# attiny85usb_4ch.net
KiCad netlist of a schematic drawn in EAGLE
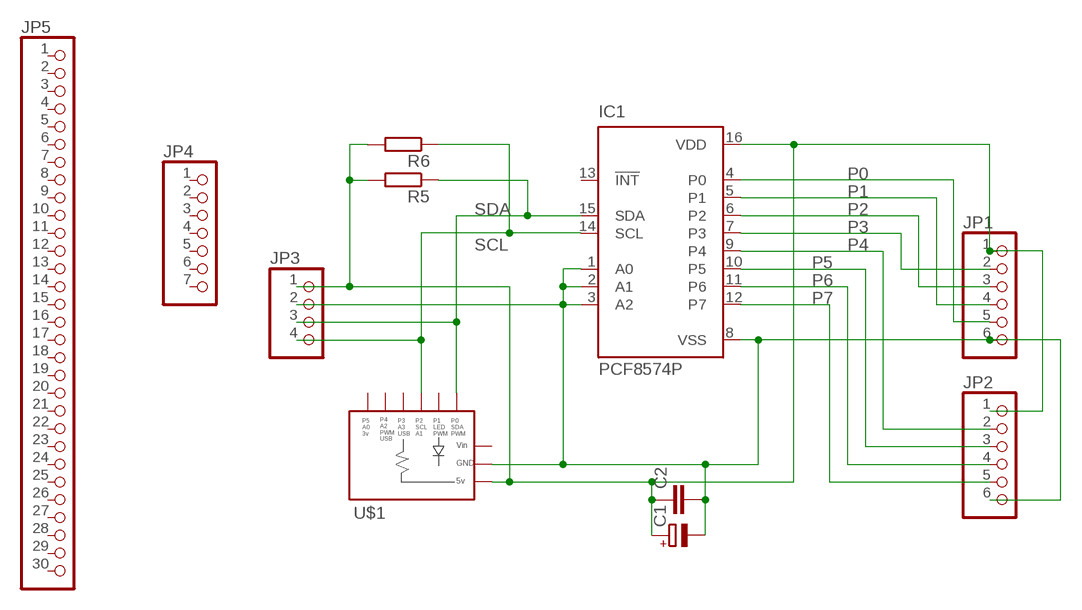
[diagram p0: schematic, sheet 1]

(export (version "E")
  (design (tool "Eeschema 10.0.6"))
  (components
    (comp (ref "C1")
      (value "CPOL-EUE2-5")
      (footprint "eagle-import:E2-5")
      (libsource (lib "eagle-import") (part "CPOL-EUE2-5"))
    )
    (comp (ref "C2")
      (value "C-EU025-050X050")
      (footprint "eagle-import:C025-050X050")
      (libsource (lib "eagle-import") (part "C-EU025-050X050"))
    )
    (comp (ref "IC1")
      (value "PCF8574P")
      (footprint "eagle-import:DIL16")
      (fields (field (name "MPN") "PCF8574PN"))
      (libsource (lib "eagle-import") (part "PCF8574P"))
    )
    (comp (ref "JP1")
      (value "PINHD-1X6")
      (footprint "eagle-import:1X06")
      (libsource (lib "eagle-import") (part "PINHD-1X6"))
    )
    (comp (ref "JP2")
      (value "PINHD-1X6/90")
      (footprint "eagle-import:1X06_90")
      (libsource (lib "eagle-import") (part "PINHD-1X6/90"))
    )
    (comp (ref "JP3")
      (value "PINHD-1X4/90")
      (footprint "eagle-import:1X04_90")
      (libsource (lib "eagle-import") (part "PINHD-1X4/90"))
    )
    (comp (ref "JP4")
      (value "PINHD-1X7")
      (footprint "eagle-import:1X07")
      (libsource (lib "eagle-import") (part "PINHD-1X7"))
    )
    (comp (ref "JP5")
      (value "PINHD-1X30")
      (footprint "eagle-import:1X30")
      (libsource (lib "eagle-import") (part "PINHD-1X30"))
    )
    (comp (ref "R5")
      (value "R-EU_0207/10")
      (footprint "eagle-import:0207_10")
      (libsource (lib "eagle-import") (part "R-EU_0207/10"))
    )
    (comp (ref "R6")
      (value "R-EU_0207/10")
      (footprint "eagle-import:0207_10")
      (libsource (lib "eagle-import") (part "R-EU_0207/10"))
    )
    (comp (ref "U$1")
      (value "DIGISPARK")
      (footprint "eagle-import:DIGISPARK")
      (libsource (lib "eagle-import") (part "DIGISPARK"))
    )
  )
  (nets
    (net (code "1") (name "/P0") (class "Default")
      (node (ref "IC1") (pin "4") (pinfunction "P0_4") (pintype "bidirectional"))
      (node (ref "JP1") (pin "5") (pinfunction "5_5") (pintype "passive"))
    )
    (net (code "2") (name "/P1") (class "Default")
      (node (ref "IC1") (pin "5") (pinfunction "P1_5") (pintype "bidirectional"))
      (node (ref "JP1") (pin "4") (pinfunction "4_4") (pintype "passive"))
    )
    (net (code "3") (name "/P2") (class "Default")
      (node (ref "IC1") (pin "6") (pinfunction "P2_6") (pintype "bidirectional"))
      (node (ref "JP1") (pin "3") (pinfunction "3_3") (pintype "passive"))
    )
    (net (code "4") (name "/P3") (class "Default")
      (node (ref "IC1") (pin "7") (pinfunction "P3_7") (pintype "bidirectional"))
      (node (ref "JP1") (pin "2") (pinfunction "2_2") (pintype "passive"))
    )
    (net (code "5") (name "/P4") (class "Default")
      (node (ref "IC1") (pin "9") (pinfunction "P4_9") (pintype "bidirectional"))
      (node (ref "JP2") (pin "2") (pinfunction "2_2") (pintype "passive"))
    )
    (net (code "6") (name "/P5") (class "Default")
      (node (ref "IC1") (pin "10") (pinfunction "P5_10") (pintype "bidirectional"))
      (node (ref "JP2") (pin "3") (pinfunction "3_3") (pintype "passive"))
    )
    (net (code "7") (name "/P6") (class "Default")
      (node (ref "IC1") (pin "11") (pinfunction "P6_11") (pintype "bidirectional"))
      (node (ref "JP2") (pin "4") (pinfunction "4_4") (pintype "passive"))
    )
    (net (code "8") (name "/P7") (class "Default")
      (node (ref "IC1") (pin "12") (pinfunction "P7_12") (pintype "bidirectional"))
      (node (ref "JP2") (pin "5") (pinfunction "5_5") (pintype "passive"))
    )
    (net (code "9") (name "/SCL") (class "Default")
      (node (ref "IC1") (pin "14") (pinfunction "SCL_14") (pintype "input"))
      (node (ref "JP3") (pin "4") (pinfunction "4_4") (pintype "passive"))
      (node (ref "R6") (pin "1") (pinfunction "1_1") (pintype "passive"))
      (node (ref "U$1") (pin "P2") (pinfunction "P2_P2") (pintype "bidirectional"))
    )
    (net (code "10") (name "/SDA") (class "Default")
      (node (ref "IC1") (pin "15") (pinfunction "SDA_15") (pintype "bidirectional"))
      (node (ref "JP3") (pin "3") (pinfunction "3_3") (pintype "passive"))
      (node (ref "R5") (pin "1") (pinfunction "1_1") (pintype "passive"))
      (node (ref "U$1") (pin "P0") (pinfunction "P0_P0") (pintype "bidirectional"))
    )
    (net (code "11") (name "/VIN") (class "Default")
      (node (ref "U$1") (pin "VIN") (pinfunction "VIN_VIN") (pintype "power_in"))
    )
    (net (code "12") (name "Net-(IC1-A0)") (class "Default")
      (node (ref "C1") (pin "-") (pinfunction "-_-") (pintype "passive"))
      (node (ref "C2") (pin "2") (pinfunction "2_2") (pintype "passive"))
      (node (ref "IC1") (pin "1") (pinfunction "A0_1") (pintype "input"))
      (node (ref "IC1") (pin "2") (pinfunction "A1_2") (pintype "input"))
      (node (ref "IC1") (pin "3") (pinfunction "A2_3") (pintype "input"))
      (node (ref "IC1") (pin "8") (pinfunction "VSS_8") (pintype "power_in"))
      (node (ref "JP1") (pin "6") (pinfunction "6_6") (pintype "passive"))
      (node (ref "JP2") (pin "6") (pinfunction "6_6") (pintype "passive"))
      (node (ref "JP3") (pin "2") (pinfunction "2_2") (pintype "passive"))
      (node (ref "U$1") (pin "GND") (pinfunction "GND_GND") (pintype "power_in"))
    )
    (net (code "13") (name "Net-(IC1-VDD)") (class "Default")
      (node (ref "C1") (pin "+") (pinfunction "+_+") (pintype "passive"))
      (node (ref "C2") (pin "1") (pinfunction "1_1") (pintype "passive"))
      (node (ref "IC1") (pin "16") (pinfunction "VDD_16") (pintype "power_in"))
      (node (ref "JP1") (pin "1") (pinfunction "1_1") (pintype "passive"))
      (node (ref "JP2") (pin "1") (pinfunction "1_1") (pintype "passive"))
      (node (ref "JP3") (pin "1") (pinfunction "1_1") (pintype "passive"))
      (node (ref "R5") (pin "2") (pinfunction "2_2") (pintype "passive"))
      (node (ref "R6") (pin "2") (pinfunction "2_2") (pintype "passive"))
      (node (ref "U$1") (pin "5V") (pinfunction "5V_5V") (pintype "power_in"))
    )
    (net (code "14") (name "unconnected-(IC1-~{INT}-Pad13)") (class "Default")
      (node (ref "IC1") (pin "13") (pinfunction "~{INT}_13") (pintype "output"))
    )
    (net (code "15") (name "unconnected-(JP4-Pad1)") (class "Default")
      (node (ref "JP4") (pin "1") (pinfunction "1_1") (pintype "passive"))
    )
    (net (code "16") (name "unconnected-(JP4-Pad2)") (class "Default")
      (node (ref "JP4") (pin "2") (pinfunction "2_2") (pintype "passive"))
    )
    (net (code "17") (name "unconnected-(JP4-Pad3)") (class "Default")
      (node (ref "JP4") (pin "3") (pinfunction "3_3") (pintype "passive"))
    )
    (net (code "18") (name "unconnected-(JP4-Pad4)") (class "Default")
      (node (ref "JP4") (pin "4") (pinfunction "4_4") (pintype "passive"))
    )
    (net (code "19") (name "unconnected-(JP4-Pad5)") (class "Default")
      (node (ref "JP4") (pin "5") (pinfunction "5_5") (pintype "passive"))
    )
    (net (code "20") (name "unconnected-(JP4-Pad6)") (class "Default")
      (node (ref "JP4") (pin "6") (pinfunction "6_6") (pintype "passive"))
    )
    (net (code "21") (name "unconnected-(JP4-Pad7)") (class "Default")
      (node (ref "JP4") (pin "7") (pinfunction "7_7") (pintype "passive"))
    )
    (net (code "22") (name "unconnected-(JP5-Pad1)") (class "Default")
      (node (ref "JP5") (pin "1") (pinfunction "1_1") (pintype "passive"))
    )
    (net (code "23") (name "unconnected-(JP5-Pad2)") (class "Default")
      (node (ref "JP5") (pin "2") (pinfunction "2_2") (pintype "passive"))
    )
    (net (code "24") (name "unconnected-(JP5-Pad3)") (class "Default")
      (node (ref "JP5") (pin "3") (pinfunction "3_3") (pintype "passive"))
    )
    (net (code "25") (name "unconnected-(JP5-Pad4)") (class "Default")
      (node (ref "JP5") (pin "4") (pinfunction "4_4") (pintype "passive"))
    )
    (net (code "26") (name "unconnected-(JP5-Pad5)") (class "Default")
      (node (ref "JP5") (pin "5") (pinfunction "5_5") (pintype "passive"))
    )
    (net (code "27") (name "unconnected-(JP5-Pad6)") (class "Default")
      (node (ref "JP5") (pin "6") (pinfunction "6_6") (pintype "passive"))
    )
    (net (code "28") (name "unconnected-(JP5-Pad7)") (class "Default")
      (node (ref "JP5") (pin "7") (pinfunction "7_7") (pintype "passive"))
    )
    (net (code "29") (name "unconnected-(JP5-Pad8)") (class "Default")
      (node (ref "JP5") (pin "8") (pinfunction "8_8") (pintype "passive"))
    )
    (net (code "30") (name "unconnected-(JP5-Pad9)") (class "Default")
      (node (ref "JP5") (pin "9") (pinfunction "9_9") (pintype "passive"))
    )
    (net (code "31") (name "unconnected-(JP5-Pad10)") (class "Default")
      (node (ref "JP5") (pin "10") (pinfunction "10_10") (pintype "passive"))
    )
    (net (code "32") (name "unconnected-(JP5-Pad11)") (class "Default")
      (node (ref "JP5") (pin "11") (pinfunction "11_11") (pintype "passive"))
    )
    (net (code "33") (name "unconnected-(JP5-Pad12)") (class "Default")
      (node (ref "JP5") (pin "12") (pinfunction "12_12") (pintype "passive"))
    )
    (net (code "34") (name "unconnected-(JP5-Pad13)") (class "Default")
      (node (ref "JP5") (pin "13") (pinfunction "13_13") (pintype "passive"))
    )
    (net (code "35") (name "unconnected-(JP5-Pad14)") (class "Default")
      (node (ref "JP5") (pin "14") (pinfunction "14_14") (pintype "passive"))
    )
    (net (code "36") (name "unconnected-(JP5-Pad15)") (class "Default")
      (node (ref "JP5") (pin "15") (pinfunction "15_15") (pintype "passive"))
    )
    (net (code "37") (name "unconnected-(JP5-Pad16)") (class "Default")
      (node (ref "JP5") (pin "16") (pinfunction "16_16") (pintype "passive"))
    )
    (net (code "38") (name "unconnected-(JP5-Pad17)") (class "Default")
      (node (ref "JP5") (pin "17") (pinfunction "17_17") (pintype "passive"))
    )
    (net (code "39") (name "unconnected-(JP5-Pad18)") (class "Default")
      (node (ref "JP5") (pin "18") (pinfunction "18_18") (pintype "passive"))
    )
    (net (code "40") (name "unconnected-(JP5-Pad19)") (class "Default")
      (node (ref "JP5") (pin "19") (pinfunction "19_19") (pintype "passive"))
    )
    (net (code "41") (name "unconnected-(JP5-Pad20)") (class "Default")
      (node (ref "JP5") (pin "20") (pinfunction "20_20") (pintype "passive"))
    )
    (net (code "42") (name "unconnected-(JP5-Pad21)") (class "Default")
      (node (ref "JP5") (pin "21") (pinfunction "21_21") (pintype "passive"))
    )
    (net (code "43") (name "unconnected-(JP5-Pad22)") (class "Default")
      (node (ref "JP5") (pin "22") (pinfunction "22_22") (pintype "passive"))
    )
    (net (code "44") (name "unconnected-(JP5-Pad23)") (class "Default")
      (node (ref "JP5") (pin "23") (pinfunction "23_23") (pintype "passive"))
    )
    (net (code "45") (name "unconnected-(JP5-Pad24)") (class "Default")
      (node (ref "JP5") (pin "24") (pinfunction "24_24") (pintype "passive"))
    )
    (net (code "46") (name "unconnected-(JP5-Pad25)") (class "Default")
      (node (ref "JP5") (pin "25") (pinfunction "25_25") (pintype "passive"))
    )
    (net (code "47") (name "unconnected-(JP5-Pad26)") (class "Default")
      (node (ref "JP5") (pin "26") (pinfunction "26_26") (pintype "passive"))
    )
    (net (code "48") (name "unconnected-(JP5-Pad27)") (class "Default")
      (node (ref "JP5") (pin "27") (pinfunction "27_27") (pintype "passive"))
    )
    (net (code "49") (name "unconnected-(JP5-Pad28)") (class "Default")
      (node (ref "JP5") (pin "28") (pinfunction "28_28") (pintype "passive"))
    )
    (net (code "50") (name "unconnected-(JP5-Pad29)") (class "Default")
      (node (ref "JP5") (pin "29") (pinfunction "29_29") (pintype "passive"))
    )
    (net (code "51") (name "unconnected-(JP5-Pad30)") (class "Default")
      (node (ref "JP5") (pin "30") (pinfunction "30_30") (pintype "passive"))
    )
    (net (code "52") (name "unconnected-(U$1-PadP1)") (class "Default")
      (node (ref "U$1") (pin "P1") (pinfunction "P1_P1") (pintype "bidirectional"))
    )
    (net (code "53") (name "unconnected-(U$1-PadP3)") (class "Default")
      (node (ref "U$1") (pin "P3") (pinfunction "P3_P3") (pintype "bidirectional"))
    )
    (net (code "54") (name "unconnected-(U$1-PadP4)") (class "Default")
      (node (ref "U$1") (pin "P4") (pinfunction "P4_P4") (pintype "bidirectional"))
    )
    (net (code "55") (name "unconnected-(U$1-PadP5)") (class "Default")
      (node (ref "U$1") (pin "P5") (pinfunction "P5_P5") (pintype "bidirectional"))
    )
  )
)
